# lm239d.net
KiCad netlist of a schematic drawn in EAGLE
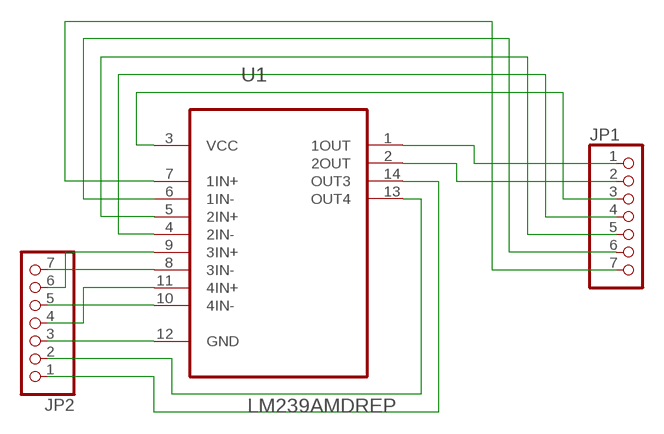
[diagram p0: schematic, sheet 1]

(export (version "E")
  (design (tool "Eeschema 10.0.6"))
  (components
    (comp (ref "JP1")
      (value "PINHD-1X7")
      (footprint "eagle-import:1X07")
      (libsource (lib "eagle-import") (part "PINHD-1X7"))
    )
    (comp (ref "JP2")
      (value "PINHD-1X7")
      (footprint "eagle-import:1X07")
      (libsource (lib "eagle-import") (part "PINHD-1X7"))
    )
    (comp (ref "U1")
      (value "LM239AMDREP")
      (footprint "eagle-import:SOIC127P600X175-14N")
      (libsource (lib "eagle-import") (part "LM239AMDREP"))
    )
  )
  (nets
    (net (code "1") (name "Net-(U1-1IN+)") (class "Default")
      (node (ref "JP1") (pin "7") (pinfunction "7_7") (pintype "passive"))
      (node (ref "U1") (pin "7") (pinfunction "1IN+_7") (pintype "input"))
    )
    (net (code "2") (name "Net-(U1-1IN-)") (class "Default")
      (node (ref "JP1") (pin "6") (pinfunction "6_6") (pintype "passive"))
      (node (ref "U1") (pin "6") (pinfunction "1IN-_6") (pintype "input"))
    )
    (net (code "3") (name "Net-(U1-1OUT)") (class "Default")
      (node (ref "JP1") (pin "1") (pinfunction "1_1") (pintype "passive"))
      (node (ref "U1") (pin "1") (pinfunction "1OUT_1") (pintype "output"))
    )
    (net (code "4") (name "Net-(U1-2IN+)") (class "Default")
      (node (ref "JP1") (pin "5") (pinfunction "5_5") (pintype "passive"))
      (node (ref "U1") (pin "5") (pinfunction "2IN+_5") (pintype "input"))
    )
    (net (code "5") (name "Net-(U1-2IN-)") (class "Default")
      (node (ref "JP1") (pin "4") (pinfunction "4_4") (pintype "passive"))
      (node (ref "U1") (pin "4") (pinfunction "2IN-_4") (pintype "input"))
    )
    (net (code "6") (name "Net-(U1-2OUT)") (class "Default")
      (node (ref "JP1") (pin "2") (pinfunction "2_2") (pintype "passive"))
      (node (ref "U1") (pin "2") (pinfunction "2OUT_2") (pintype "output"))
    )
    (net (code "7") (name "Net-(U1-3IN+)") (class "Default")
      (node (ref "JP2") (pin "6") (pinfunction "6_6") (pintype "passive"))
      (node (ref "U1") (pin "9") (pinfunction "3IN+_9") (pintype "input"))
    )
    (net (code "8") (name "Net-(U1-3IN-)") (class "Default")
      (node (ref "JP2") (pin "7") (pinfunction "7_7") (pintype "passive"))
      (node (ref "U1") (pin "8") (pinfunction "3IN-_8") (pintype "input"))
    )
    (net (code "9") (name "Net-(U1-4IN+)") (class "Default")
      (node (ref "JP2") (pin "4") (pinfunction "4_4") (pintype "passive"))
      (node (ref "U1") (pin "11") (pinfunction "4IN+_11") (pintype "input"))
    )
    (net (code "10") (name "Net-(U1-4IN-)") (class "Default")
      (node (ref "JP2") (pin "5") (pinfunction "5_5") (pintype "passive"))
      (node (ref "U1") (pin "10") (pinfunction "4IN-_10") (pintype "input"))
    )
    (net (code "11") (name "Net-(U1-GND)") (class "Default")
      (node (ref "JP2") (pin "3") (pinfunction "3_3") (pintype "passive"))
      (node (ref "U1") (pin "12") (pinfunction "GND_12") (pintype "passive"))
    )
    (net (code "12") (name "Net-(U1-OUT3)") (class "Default")
      (node (ref "JP2") (pin "1") (pinfunction "1_1") (pintype "passive"))
      (node (ref "U1") (pin "14") (pinfunction "OUT3_14") (pintype "output"))
    )
    (net (code "13") (name "Net-(U1-OUT4)") (class "Default")
      (node (ref "JP2") (pin "2") (pinfunction "2_2") (pintype "passive"))
      (node (ref "U1") (pin "13") (pinfunction "OUT4_13") (pintype "output"))
    )
    (net (code "14") (name "Net-(U1-VCC)") (class "Default")
      (node (ref "JP1") (pin "3") (pinfunction "3_3") (pintype "passive"))
      (node (ref "U1") (pin "3") (pinfunction "VCC_3") (pintype "power_in"))
    )
  )
)
